# MCU.net
KiCad netlist of a schematic drawn in Altium Designer
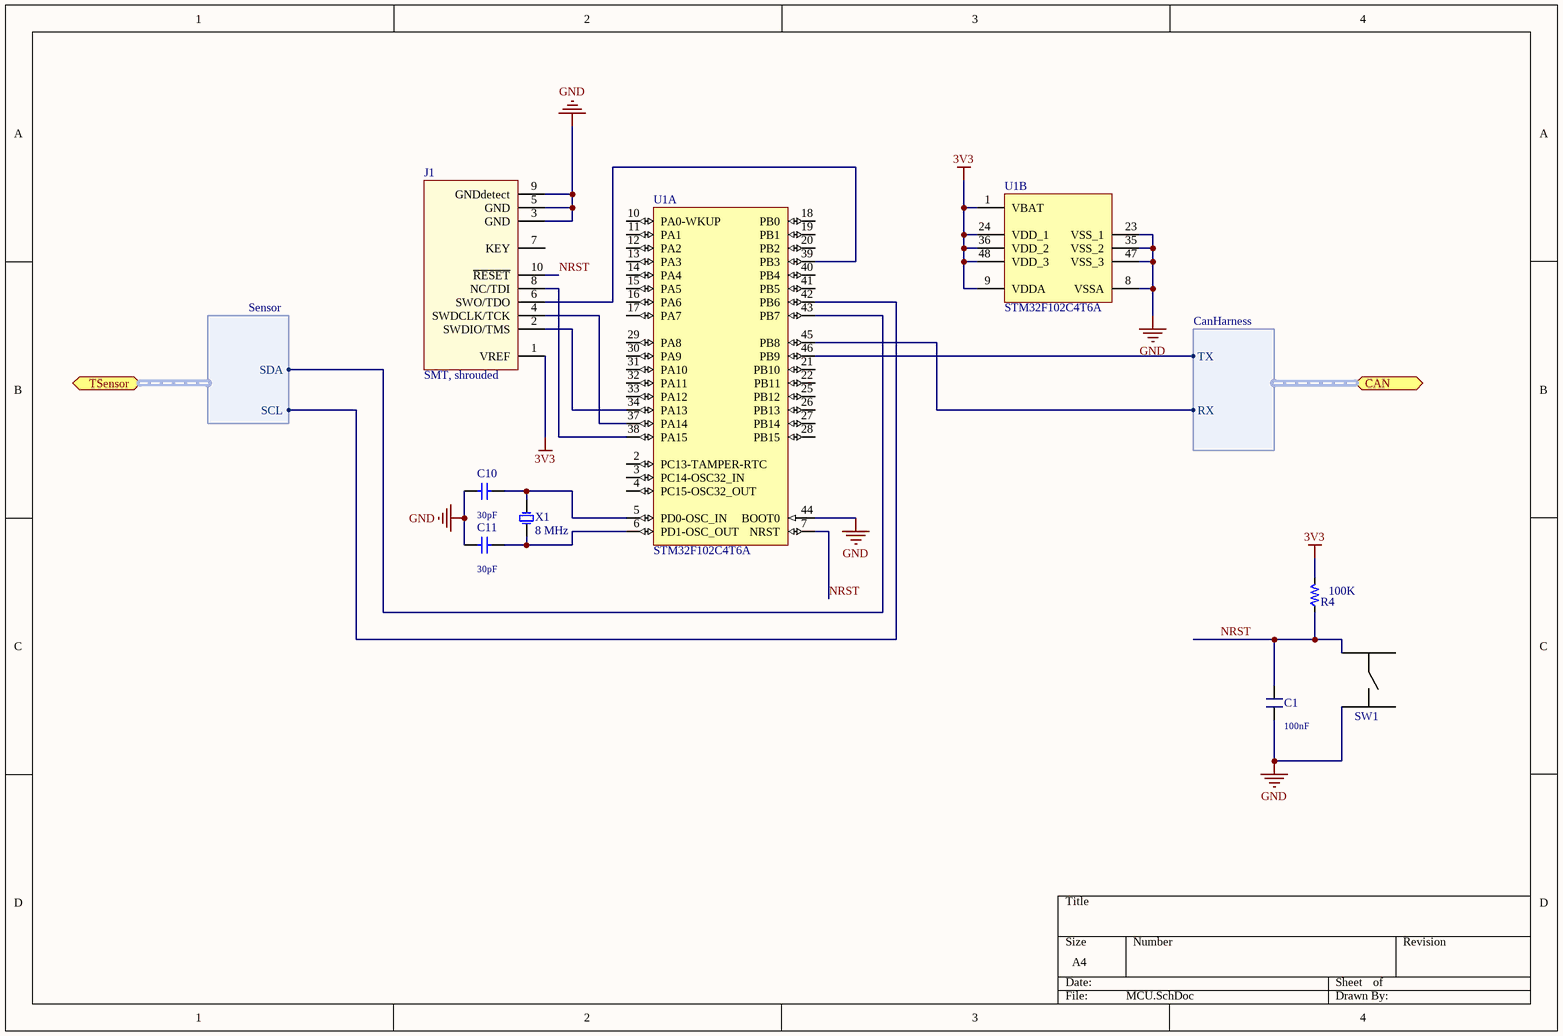
[diagram p0: MCU.SchDoc]

(export (version "E")
  (design (tool "Eeschema 10.0.6"))
  (components
    (comp (ref "C1")
      (value "SCH_GENERIC_CAPACITOR_0603")
      (footprint "PCB_GENERIC_SMD_0603")
      (description "Generic SMD capacitor 0603")
      (fields (field (name "TOLERANCE") "*%") (field (name "CAPACITANCE") "100nF"))
      (libsource (lib "") (part "SCH_GENERIC_CAPACITOR_0603_1"))
    )
    (comp (ref "C10")
      (value "SCH_GENERIC_CAPACITOR_0603")
      (footprint "PCB_GENERIC_SMD_0603")
      (description "Generic SMD capacitor 0603")
      (fields
        (field (name "TOLERANCE") "*%")
        (field (name "CAPACITANCE") "30pF")
        (field (name "VOLTAGE") "*V")
      )
      (libsource (lib "Generic 0603 Capacitor") (part "SCH_GENERIC_CAPACITOR_0603"))
    )
    (comp (ref "C11")
      (value "SCH_GENERIC_CAPACITOR_0603")
      (footprint "PCB_GENERIC_SMD_0603")
      (description "Generic SMD capacitor 0603")
      (fields (field (name "TOLERANCE") "*%") (field (name "CAPACITANCE") "30pF"))
      (libsource (lib "Generic 0603 Capacitor") (part "SCH_GENERIC_CAPACITOR_0603"))
    )
    (comp (ref "J1")
      (value "SMT, shrouded")
      (footprint "CONN-50mil-10POS-SMD")
      (description "ARM Cortex-M 10pin connector,shrouded,SMT")
      (libsource (lib "CONN-50mil-cortexM") (part "conn_0.050{dblquote}_cortexM"))
    )
    (comp (ref "R4")
      (value "SCH_GENERIC_RESISTOR_0603")
      (footprint "PCB_GENERIC_SMD_0603")
      (description "Generic SMD resistor 0603")
      (fields (field (name "RESISTANCE") "100K"))
      (libsource (lib "Generic 0603 Resistor") (part "SCH_GENERIC_RESISTOR_0603"))
    )
    (comp (ref "SW1")
      (value "Tactile Switch")
      (footprint "C&K 4 pin Tactile Switch")
      (libsource (lib "C&K 4 Pin Tactile Switch") (part "C&K Tactile Switch"))
    )
    (comp (ref "U1")
      (value "STM32F102C4T6A")
      (footprint "STM-LQFP48_N")
      (libsource (lib "STMicroelectronics STM32 F1") (part "STM32F102C4T6A"))
    )
    (comp (ref "X1")
      (value "8 MHz")
      (footprint "CRYSTAL_8MHZ")
      (description "8MHz ±30ppm 20pF Crystal")
      (libsource (lib "Foxslf 8MHz Crystal") (part "XTAL_TH_8MHz"))
    )
  )
  (nets
    (net (code "3") (name "/NRST") (class "Default")
      (node (ref "C1") (pin "2") (pinfunction "2_2") (pintype "passive"))
      (node (ref "J1") (pin "10") (pinfunction "~{RESET}_10") (pintype "passive"))
      (node (ref "R4") (pin "1") (pinfunction "1_1") (pintype "passive"))
      (node (ref "SW1") (pin "1") (pintype "passive"))
      (node (ref "U1") (pin "7") (pinfunction "NRST_7") (pintype "bidirectional"))
    )
    (net (code "4") (name "/RX") (class "Default")
      (node (ref "U1") (pin "45") (pinfunction "PB8_45") (pintype "bidirectional"))
    )
    (net (code "5") (name "/SCL") (class "Default")
      (node (ref "U1") (pin "42") (pinfunction "PB6_42") (pintype "bidirectional"))
    )
    (net (code "6") (name "/SDA") (class "Default")
      (node (ref "U1") (pin "43") (pinfunction "PB7_43") (pintype "bidirectional"))
    )
    (net (code "7") (name "/TX") (class "Default")
      (node (ref "U1") (pin "46") (pinfunction "PB9_46") (pintype "bidirectional"))
    )
    (net (code "10") (name "3V3") (class "Default")
      (node (ref "J1") (pin "1") (pinfunction "VREF_1") (pintype "passive"))
      (node (ref "R4") (pin "2") (pinfunction "2_2") (pintype "passive"))
      (node (ref "U1") (pin "1") (pinfunction "VBAT_1") (pintype "power_in"))
      (node (ref "U1") (pin "24") (pinfunction "VDD_1_24") (pintype "power_in"))
      (node (ref "U1") (pin "36") (pinfunction "VDD_2_36") (pintype "power_in"))
      (node (ref "U1") (pin "48") (pinfunction "VDD_3_48") (pintype "power_in"))
      (node (ref "U1") (pin "9") (pinfunction "VDDA_9") (pintype "power_in"))
    )
    (net (code "11") (name "GND") (class "Default")
      (node (ref "C1") (pin "1") (pinfunction "1_1") (pintype "passive"))
      (node (ref "C10") (pin "2") (pinfunction "2_2") (pintype "passive"))
      (node (ref "C11") (pin "2") (pinfunction "2_2") (pintype "passive"))
      (node (ref "J1") (pin "3") (pinfunction "GND_3") (pintype "passive"))
      (node (ref "J1") (pin "5") (pinfunction "GND_5") (pintype "passive"))
      (node (ref "J1") (pin "9") (pinfunction "GNDdetect_9") (pintype "passive"))
      (node (ref "SW1") (pin "3") (pinfunction "3_3") (pintype "passive"))
      (node (ref "U1") (pin "23") (pinfunction "VSS_1_23") (pintype "power_in"))
      (node (ref "U1") (pin "35") (pinfunction "VSS_2_35") (pintype "power_in"))
      (node (ref "U1") (pin "44") (pinfunction "BOOT0_44") (pintype "input"))
      (node (ref "U1") (pin "47") (pinfunction "VSS_3_47") (pintype "power_in"))
      (node (ref "U1") (pin "8") (pinfunction "VSSA_8") (pintype "power_in"))
    )
    (net (code "12") (name "Net-(J1-NC{slash}TDI)") (class "Default")
      (node (ref "J1") (pin "8") (pinfunction "NC/TDI_8") (pintype "passive"))
      (node (ref "U1") (pin "38") (pinfunction "PA15_38") (pintype "bidirectional"))
    )
    (net (code "13") (name "Net-(J1-SWDCLK{slash}TCK)") (class "Default")
      (node (ref "J1") (pin "4") (pinfunction "SWDCLK/TCK_4") (pintype "passive"))
      (node (ref "U1") (pin "37") (pinfunction "PA14_37") (pintype "bidirectional"))
    )
    (net (code "14") (name "Net-(J1-SWDIO{slash}TMS)") (class "Default")
      (node (ref "J1") (pin "2") (pinfunction "SWDIO/TMS_2") (pintype "passive"))
      (node (ref "U1") (pin "34") (pinfunction "PA13_34") (pintype "bidirectional"))
    )
    (net (code "15") (name "Net-(J1-SWO{slash}TDO)") (class "Default")
      (node (ref "J1") (pin "6") (pinfunction "SWO/TDO_6") (pintype "passive"))
      (node (ref "U1") (pin "39") (pinfunction "PB3_39") (pintype "bidirectional"))
    )
    (net (code "16") (name "Net-(U1A-PD0-OSC_IN)") (class "Default")
      (node (ref "C10") (pin "1") (pinfunction "1_1") (pintype "passive"))
      (node (ref "U1") (pin "5") (pinfunction "PD0-OSC_IN_5") (pintype "bidirectional"))
      (node (ref "X1") (pin "2") (pintype "passive"))
    )
    (net (code "17") (name "Net-(U1A-PD1-OSC_OUT)") (class "Default")
      (node (ref "C11") (pin "1") (pinfunction "1_1") (pintype "passive"))
      (node (ref "U1") (pin "6") (pinfunction "PD1-OSC_OUT_6") (pintype "bidirectional"))
      (node (ref "X1") (pin "1") (pintype "passive"))
    )
    (net (code "18") (name "unconnected-(J1-KEY-Pad7)") (class "Default")
      (node (ref "J1") (pin "7") (pinfunction "KEY_7") (pintype "passive"))
    )
    (net (code "19") (name "unconnected-(SW1-Pad2)") (class "Default")
      (node (ref "SW1") (pin "2") (pinfunction "2_2") (pintype "passive"))
    )
    (net (code "20") (name "unconnected-(SW1-Pad4)") (class "Default")
      (node (ref "SW1") (pin "4") (pinfunction "4_4") (pintype "passive"))
    )
    (net (code "21") (name "unconnected-(U1A-PA0-WKUP-Pad10)") (class "Default")
      (node (ref "U1") (pin "10") (pinfunction "PA0-WKUP_10") (pintype "bidirectional"))
    )
    (net (code "22") (name "unconnected-(U1A-PA1-Pad11)") (class "Default")
      (node (ref "U1") (pin "11") (pinfunction "PA1_11") (pintype "bidirectional"))
    )
    (net (code "23") (name "unconnected-(U1A-PA2-Pad12)") (class "Default")
      (node (ref "U1") (pin "12") (pinfunction "PA2_12") (pintype "bidirectional"))
    )
    (net (code "24") (name "unconnected-(U1A-PA3-Pad13)") (class "Default")
      (node (ref "U1") (pin "13") (pinfunction "PA3_13") (pintype "bidirectional"))
    )
    (net (code "25") (name "unconnected-(U1A-PA4-Pad14)") (class "Default")
      (node (ref "U1") (pin "14") (pinfunction "PA4_14") (pintype "bidirectional"))
    )
    (net (code "26") (name "unconnected-(U1A-PA5-Pad15)") (class "Default")
      (node (ref "U1") (pin "15") (pinfunction "PA5_15") (pintype "bidirectional"))
    )
    (net (code "27") (name "unconnected-(U1A-PA6-Pad16)") (class "Default")
      (node (ref "U1") (pin "16") (pinfunction "PA6_16") (pintype "bidirectional"))
    )
    (net (code "28") (name "unconnected-(U1A-PA7-Pad17)") (class "Default")
      (node (ref "U1") (pin "17") (pinfunction "PA7_17") (pintype "bidirectional"))
    )
    (net (code "29") (name "unconnected-(U1A-PA8-Pad29)") (class "Default")
      (node (ref "U1") (pin "29") (pinfunction "PA8_29") (pintype "bidirectional"))
    )
    (net (code "30") (name "unconnected-(U1A-PA9-Pad30)") (class "Default")
      (node (ref "U1") (pin "30") (pinfunction "PA9_30") (pintype "bidirectional"))
    )
    (net (code "31") (name "unconnected-(U1A-PA10-Pad31)") (class "Default")
      (node (ref "U1") (pin "31") (pinfunction "PA10_31") (pintype "bidirectional"))
    )
    (net (code "32") (name "unconnected-(U1A-PA11-Pad32)") (class "Default")
      (node (ref "U1") (pin "32") (pinfunction "PA11_32") (pintype "bidirectional"))
    )
    (net (code "33") (name "unconnected-(U1A-PA12-Pad33)") (class "Default")
      (node (ref "U1") (pin "33") (pinfunction "PA12_33") (pintype "bidirectional"))
    )
    (net (code "34") (name "unconnected-(U1A-PB0-Pad18)") (class "Default")
      (node (ref "U1") (pin "18") (pinfunction "PB0_18") (pintype "bidirectional"))
    )
    (net (code "35") (name "unconnected-(U1A-PB1-Pad19)") (class "Default")
      (node (ref "U1") (pin "19") (pinfunction "PB1_19") (pintype "bidirectional"))
    )
    (net (code "36") (name "unconnected-(U1A-PB2-Pad20)") (class "Default")
      (node (ref "U1") (pin "20") (pinfunction "PB2_20") (pintype "bidirectional"))
    )
    (net (code "37") (name "unconnected-(U1A-PB4-Pad40)") (class "Default")
      (node (ref "U1") (pin "40") (pinfunction "PB4_40") (pintype "bidirectional"))
    )
    (net (code "38") (name "unconnected-(U1A-PB5-Pad41)") (class "Default")
      (node (ref "U1") (pin "41") (pinfunction "PB5_41") (pintype "bidirectional"))
    )
    (net (code "39") (name "unconnected-(U1A-PB10-Pad21)") (class "Default")
      (node (ref "U1") (pin "21") (pinfunction "PB10_21") (pintype "bidirectional"))
    )
    (net (code "40") (name "unconnected-(U1A-PB11-Pad22)") (class "Default")
      (node (ref "U1") (pin "22") (pinfunction "PB11_22") (pintype "bidirectional"))
    )
    (net (code "41") (name "unconnected-(U1A-PB12-Pad25)") (class "Default")
      (node (ref "U1") (pin "25") (pinfunction "PB12_25") (pintype "bidirectional"))
    )
    (net (code "42") (name "unconnected-(U1A-PB13-Pad26)") (class "Default")
      (node (ref "U1") (pin "26") (pinfunction "PB13_26") (pintype "bidirectional"))
    )
    (net (code "43") (name "unconnected-(U1A-PB14-Pad27)") (class "Default")
      (node (ref "U1") (pin "27") (pinfunction "PB14_27") (pintype "bidirectional"))
    )
    (net (code "44") (name "unconnected-(U1A-PB15-Pad28)") (class "Default")
      (node (ref "U1") (pin "28") (pinfunction "PB15_28") (pintype "bidirectional"))
    )
    (net (code "45") (name "unconnected-(U1A-PC13-TAMPER-RTC-Pad2)") (class "Default")
      (node (ref "U1") (pin "2") (pinfunction "PC13-TAMPER-RTC_2") (pintype "bidirectional"))
    )
    (net (code "46") (name "unconnected-(U1A-PC14-OSC32_IN-Pad3)") (class "Default")
      (node (ref "U1") (pin "3") (pinfunction "PC14-OSC32_IN_3") (pintype "bidirectional"))
    )
    (net (code "47") (name "unconnected-(U1A-PC15-OSC32_OUT-Pad4)") (class "Default")
      (node (ref "U1") (pin "4") (pinfunction "PC15-OSC32_OUT_4") (pintype "bidirectional"))
    )
  )
)
